# i2c-relais.net
KiCad netlist of a schematic drawn in EAGLE
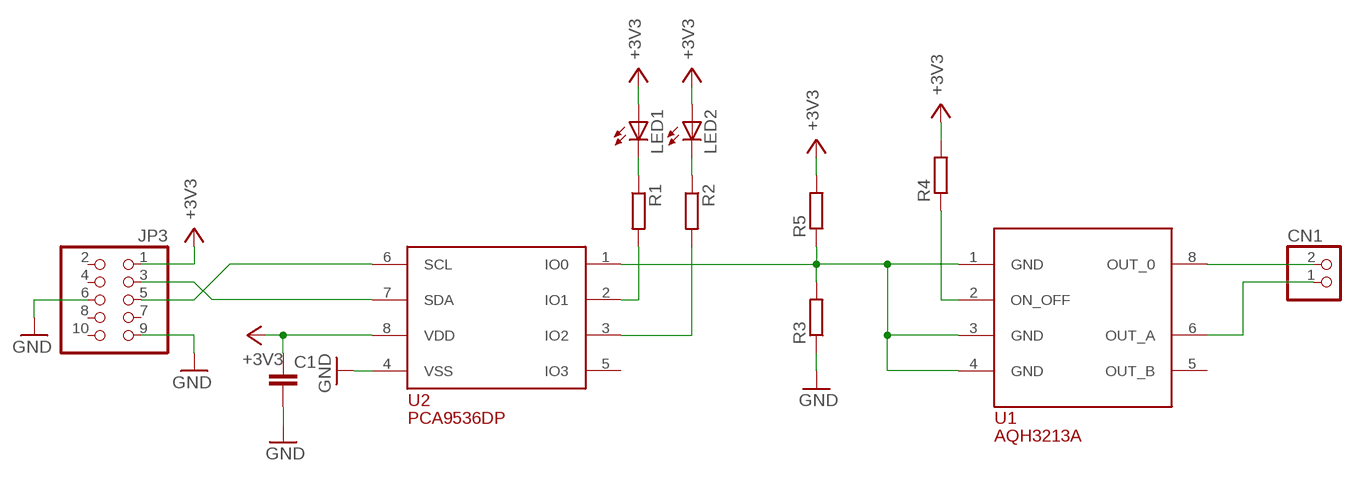
[diagram p0: schematic, sheet 1]

(export (version "E")
  (design (tool "Eeschema 10.0.6"))
  (components
    (comp (ref "C1")
      (value "C-EUC0805")
      (footprint "eagle-import:C0805")
      (libsource (lib "eagle-import") (part "C-EUC0805"))
    )
    (comp (ref "CN1")
      (value "JST_2PIN-SMT-RA")
      (footprint "eagle-import:JST-PH-2-SMT-RA")
      (libsource (lib "eagle-import") (part "JST_2PIN-SMT-RA"))
    )
    (comp (ref "JP3")
      (value "PINHD-2X5")
      (footprint "eagle-import:2X05")
      (libsource (lib "eagle-import") (part "PINHD-2X5"))
    )
    (comp (ref "LED1")
      (value "LEDCHIPLED_0805")
      (footprint "eagle-import:CHIPLED_0805")
      (libsource (lib "eagle-import") (part "LEDCHIPLED_0805"))
    )
    (comp (ref "LED2")
      (value "LEDCHIPLED_0805")
      (footprint "eagle-import:CHIPLED_0805")
      (libsource (lib "eagle-import") (part "LEDCHIPLED_0805"))
    )
    (comp (ref "R1")
      (value "R-EU_M0805")
      (footprint "eagle-import:M0805")
      (libsource (lib "eagle-import") (part "R-EU_M0805"))
    )
    (comp (ref "R2")
      (value "R-EU_M0805")
      (footprint "eagle-import:M0805")
      (libsource (lib "eagle-import") (part "R-EU_M0805"))
    )
    (comp (ref "R3")
      (value "R-EU_M0805")
      (footprint "eagle-import:M0805")
      (libsource (lib "eagle-import") (part "R-EU_M0805"))
    )
    (comp (ref "R4")
      (value "R-EU_M0805")
      (footprint "eagle-import:M0805")
      (libsource (lib "eagle-import") (part "R-EU_M0805"))
    )
    (comp (ref "R5")
      (value "R-EU_M0805")
      (footprint "eagle-import:M0805")
      (libsource (lib "eagle-import") (part "R-EU_M0805"))
    )
    (comp (ref "U1")
      (value "AQH3213A")
      (footprint "eagle-import:DIP8")
      (libsource (lib "eagle-import") (part "AQH-SSD"))
    )
    (comp (ref "U2")
      (value "PCA9536DP")
      (footprint "eagle-import:TSSOP8")
      (libsource (lib "eagle-import") (part "PCA9536DP"))
    )
  )
  (nets
    (net (code "1") (name "+3V3") (class "Default")
      (node (ref "C1") (pin "1") (pinfunction "1_1") (pintype "passive"))
      (node (ref "JP3") (pin "1") (pinfunction "1_1") (pintype "passive"))
      (node (ref "LED1") (pin "A") (pinfunction "A_A") (pintype "passive"))
      (node (ref "LED2") (pin "A") (pinfunction "A_A") (pintype "passive"))
      (node (ref "R4") (pin "2") (pinfunction "2_2") (pintype "passive"))
      (node (ref "R5") (pin "2") (pinfunction "2_2") (pintype "passive"))
      (node (ref "U2") (pin "8") (pinfunction "VDD_8") (pintype "power_in"))
    )
    (net (code "2") (name "GND") (class "Default")
      (node (ref "C1") (pin "2") (pinfunction "2_2") (pintype "passive"))
      (node (ref "JP3") (pin "6") (pinfunction "6_6") (pintype "passive"))
      (node (ref "JP3") (pin "9") (pinfunction "9_9") (pintype "passive"))
      (node (ref "R3") (pin "1") (pinfunction "1_1") (pintype "passive"))
      (node (ref "U2") (pin "4") (pinfunction "VSS_4") (pintype "power_in"))
    )
    (net (code "3") (name "Net-(CN1-1)") (class "Default")
      (node (ref "CN1") (pin "2") (pinfunction "1_2") (pintype "passive"))
      (node (ref "U1") (pin "8") (pinfunction "OUT_0_8") (pintype "bidirectional"))
    )
    (net (code "4") (name "Net-(CN1-2)") (class "Default")
      (node (ref "CN1") (pin "1") (pinfunction "2_1") (pintype "passive"))
      (node (ref "U1") (pin "6") (pinfunction "OUT_A_6") (pintype "bidirectional"))
    )
    (net (code "5") (name "Net-(LED1-PadC)") (class "Default")
      (node (ref "LED1") (pin "C") (pinfunction "C_C") (pintype "passive"))
      (node (ref "R1") (pin "1") (pinfunction "1_1") (pintype "passive"))
    )
    (net (code "6") (name "Net-(LED2-PadC)") (class "Default")
      (node (ref "LED2") (pin "C") (pinfunction "C_C") (pintype "passive"))
      (node (ref "R2") (pin "1") (pinfunction "1_1") (pintype "passive"))
    )
    (net (code "7") (name "Net-(U1-ON_OFF)") (class "Default")
      (node (ref "R4") (pin "1") (pinfunction "1_1") (pintype "passive"))
      (node (ref "U1") (pin "2") (pinfunction "ON_OFF_2") (pintype "bidirectional"))
    )
    (net (code "8") (name "Net-(U2-IO0)") (class "Default")
      (node (ref "R3") (pin "2") (pinfunction "2_2") (pintype "passive"))
      (node (ref "R5") (pin "1") (pinfunction "1_1") (pintype "passive"))
      (node (ref "U1") (pin "1") (pinfunction "GND_1") (pintype "bidirectional"))
      (node (ref "U1") (pin "3") (pinfunction "GND_3") (pintype "bidirectional"))
      (node (ref "U1") (pin "4") (pinfunction "GND_4") (pintype "bidirectional"))
      (node (ref "U2") (pin "1") (pinfunction "IO0_1") (pintype "bidirectional"))
    )
    (net (code "9") (name "Net-(U2-IO1)") (class "Default")
      (node (ref "R1") (pin "2") (pinfunction "2_2") (pintype "passive"))
      (node (ref "U2") (pin "2") (pinfunction "IO1_2") (pintype "bidirectional"))
    )
    (net (code "10") (name "Net-(U2-IO2)") (class "Default")
      (node (ref "R2") (pin "2") (pinfunction "2_2") (pintype "passive"))
      (node (ref "U2") (pin "3") (pinfunction "IO2_3") (pintype "bidirectional"))
    )
    (net (code "11") (name "Net-(U2-SCL)") (class "Default")
      (node (ref "JP3") (pin "5") (pinfunction "5_5") (pintype "passive"))
      (node (ref "U2") (pin "6") (pinfunction "SCL_6") (pintype "bidirectional"))
    )
    (net (code "12") (name "Net-(U2-SDA)") (class "Default")
      (node (ref "JP3") (pin "3") (pinfunction "3_3") (pintype "passive"))
      (node (ref "U2") (pin "7") (pinfunction "SDA_7") (pintype "bidirectional"))
    )
    (net (code "13") (name "unconnected-(JP3-Pad2)") (class "Default")
      (node (ref "JP3") (pin "2") (pinfunction "2_2") (pintype "passive"))
    )
    (net (code "14") (name "unconnected-(JP3-Pad4)") (class "Default")
      (node (ref "JP3") (pin "4") (pinfunction "4_4") (pintype "passive"))
    )
    (net (code "15") (name "unconnected-(JP3-Pad7)") (class "Default")
      (node (ref "JP3") (pin "7") (pinfunction "7_7") (pintype "passive"))
    )
    (net (code "16") (name "unconnected-(JP3-Pad8)") (class "Default")
      (node (ref "JP3") (pin "8") (pinfunction "8_8") (pintype "passive"))
    )
    (net (code "17") (name "unconnected-(JP3-Pad10)") (class "Default")
      (node (ref "JP3") (pin "10") (pinfunction "10_10") (pintype "passive"))
    )
    (net (code "18") (name "unconnected-(U1-OUT_B-Pad5)") (class "Default")
      (node (ref "U1") (pin "5") (pinfunction "OUT_B_5") (pintype "bidirectional"))
    )
    (net (code "19") (name "unconnected-(U2-IO3-Pad5)") (class "Default")
      (node (ref "U2") (pin "5") (pinfunction "IO3_5") (pintype "bidirectional"))
    )
  )
)
